# MCU_scm.net
KiCad netlist of a schematic drawn in Altium Designer
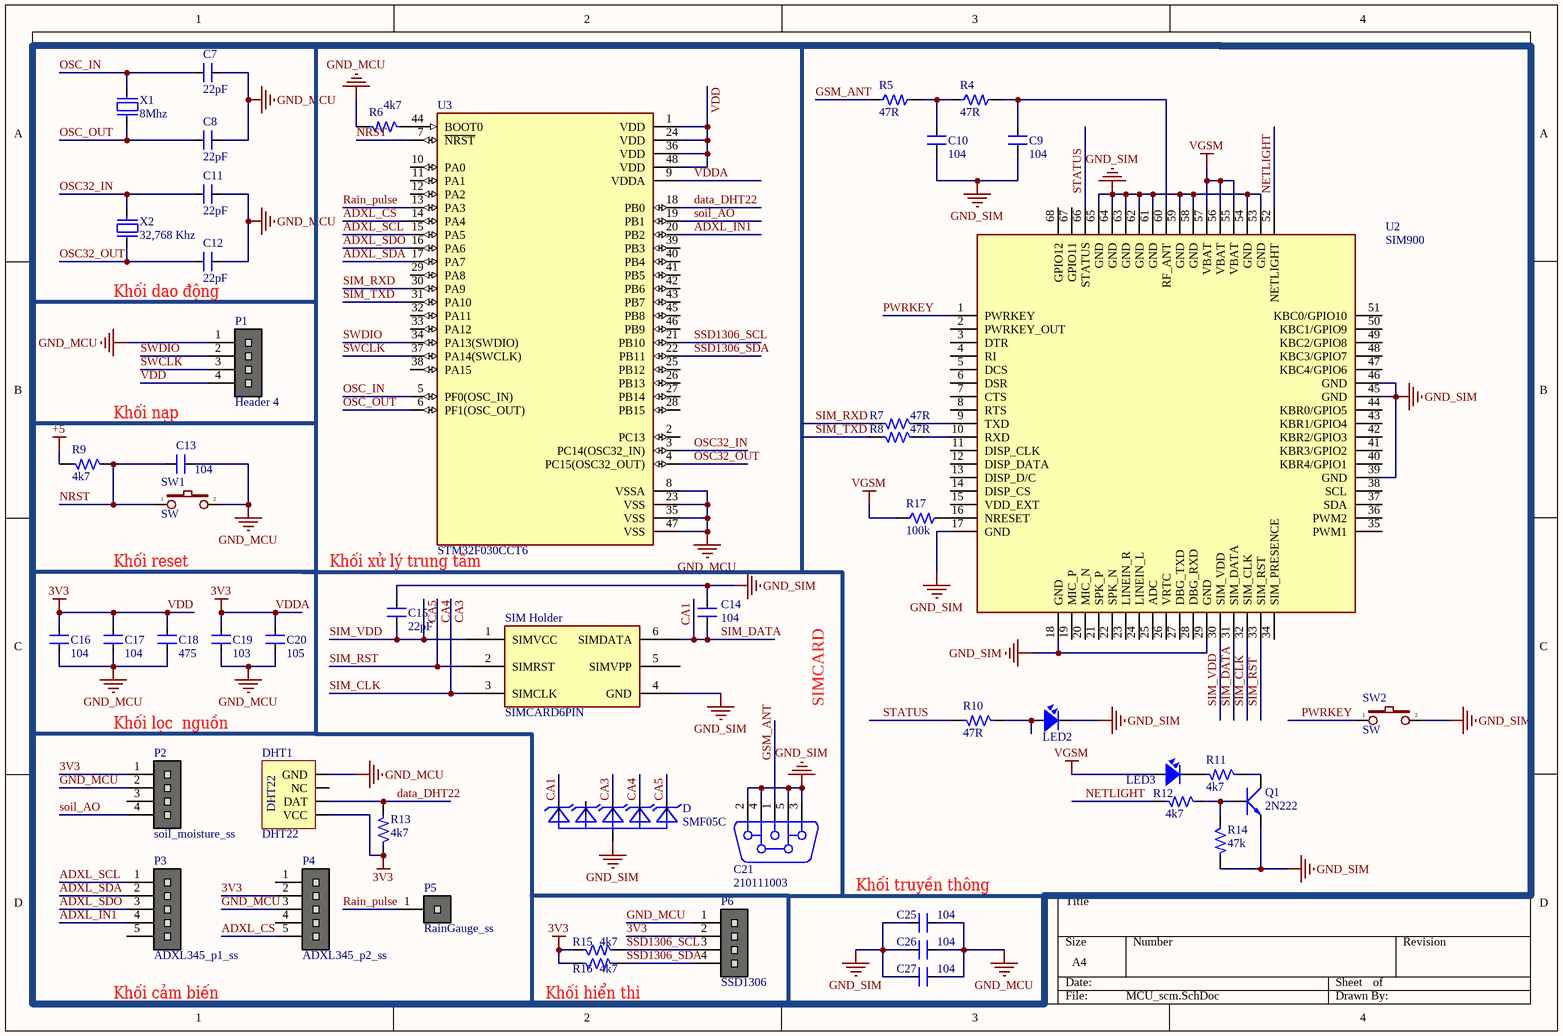
[diagram p0: MCU_scm.SchDoc]

(export (version "E")
  (design (tool "Eeschema 10.0.6"))
  (components
    (comp (ref "C7")
      (value "22pF")
      (footprint "CN1.5")
      (description "Cap np 682pF => 104pF")
      (libsource (lib "syhaunguyen") (part "CN1.5"))
    )
    (comp (ref "C8")
      (value "22pF")
      (footprint "CN1.5")
      (description "Cap np 682pF => 104pF")
      (libsource (lib "syhaunguyen") (part "CN1.5"))
    )
    (comp (ref "C9")
      (value "104")
      (footprint "SM-0805")
      (description "Cap SMD")
      (libsource (lib "syhaunguyen") (part "CM"))
    )
    (comp (ref "C10")
      (value "104")
      (footprint "SM-0805")
      (description "Cap SMD")
      (libsource (lib "syhaunguyen") (part "CM"))
    )
    (comp (ref "C11")
      (value "22pF")
      (footprint "CN1.5")
      (description "Cap np 682pF => 104pF")
      (libsource (lib "syhaunguyen") (part "CN1.5"))
    )
    (comp (ref "C12")
      (value "22pF")
      (footprint "CN1.5")
      (description "Cap np 682pF => 104pF")
      (libsource (lib "syhaunguyen") (part "CN1.5"))
    )
    (comp (ref "C13")
      (value "104")
      (footprint "SM-0805")
      (description "Cap SMD")
      (libsource (lib "syhaunguyen") (part "CM"))
    )
    (comp (ref "C14")
      (value "104")
      (footprint "SM-0805")
      (description "Cap SMD")
      (libsource (lib "syhaunguyen") (part "CM"))
    )
    (comp (ref "C15")
      (value "22pF")
      (footprint "SM-0805")
      (description "Cap SMD")
      (libsource (lib "syhaunguyen") (part "CM"))
    )
    (comp (ref "C16")
      (value "104")
      (footprint "SM-0805")
      (description "Cap SMD")
      (libsource (lib "syhaunguyen") (part "CM"))
    )
    (comp (ref "C17")
      (value "104")
      (footprint "SM-0805")
      (description "Cap SMD")
      (libsource (lib "syhaunguyen") (part "CM"))
    )
    (comp (ref "C18")
      (value "475")
      (footprint "SM-0805")
      (description "Cap SMD")
      (libsource (lib "syhaunguyen") (part "CM"))
    )
    (comp (ref "C19")
      (value "103")
      (footprint "SM-0805")
      (description "Cap SMD")
      (libsource (lib "syhaunguyen") (part "CM"))
    )
    (comp (ref "C20")
      (value "105")
      (footprint "SM-0805")
      (description "Cap SMD")
      (libsource (lib "syhaunguyen") (part "CM"))
    )
    (comp (ref "C21")
      (value "210111003")
      (footprint "SMA-RA")
      (description "CONNECTOR ANTEN")
      (fields
        (field (name "MANUFACTURER") "Würth Elektronik eiSos GmbH")
        (field (name "CREATED BY") "Christin Zierenner")
      )
      (libsource (lib "TechMT.VN_Lib_Project v2") (part "CON Ant"))
    )
    (comp (ref "C25")
      (value "104")
      (footprint "SM-0805")
      (description "Cap SMD")
      (libsource (lib "syhaunguyen") (part "CM"))
    )
    (comp (ref "C26")
      (value "104")
      (footprint "SM-0805")
      (description "Cap SMD")
      (libsource (lib "syhaunguyen") (part "CM"))
    )
    (comp (ref "C27")
      (value "104")
      (footprint "SM-0805")
      (description "Cap SMD")
      (libsource (lib "syhaunguyen") (part "CM"))
    )
    (comp (ref "D")
      (value "SMF05C")
      (footprint "SC70-6")
      (description "12.5V Clamp 8A _8/20Âµs_ Ipp Tvs Diode Surface Mount SC-88/SC70-6/SOT-363")
      (fields (field (name "MF") "ON Semiconductor"))
      (libsource (lib "SMF05C") (part "SMF05C"))
    )
    (comp (ref "DHT1")
      (value "DHT22")
      (footprint "DHT22")
      (fields
        (field (name "MANUFACTURER") "Würth Elektronik eiSos GmbH")
        (field (name "PARTNO") "613004143121")
        (field (name "CREATED BY") "Karrer Zheng")
      )
      (libsource (lib "TechMT.VN_Lib_Project v2") (part "DHT22"))
    )
    (comp (ref "LED2")
      (value "LED")
      (footprint "LED-0805-Green")
      (libsource (lib "TechMT.VN_Lib_Project v2") (part "LED SMD"))
    )
    (comp (ref "LED3")
      (value "LED")
      (footprint "LED-0805-Green")
      (libsource (lib "TechMT.VN_Lib_Project v2") (part "LED SMD"))
    )
    (comp (ref "P1")
      (value "Header 4")
      (footprint "HDR 1X4")
      (description "Header, 4-Pin")
      (libsource (lib "Ayric connectors") (part "Header 4"))
    )
    (comp (ref "P2")
      (value "soil_moisture_ss")
      (footprint "HDR 1X4")
      (description "Header, 4-Pin")
      (libsource (lib "Ayric connectors") (part "Header 4"))
    )
    (comp (ref "P3")
      (value "ADXL345_p1_ss")
      (footprint "HDR 1X5")
      (description "Header, 5-Pin")
      (libsource (lib "Ayric connectors") (part "Header 5"))
    )
    (comp (ref "P4")
      (value "ADXL345_p2_ss")
      (footprint "HDR 1X5")
      (description "Header, 5-Pin")
      (libsource (lib "Ayric connectors") (part "Header 5"))
    )
    (comp (ref "P5")
      (value "RainGauge_ss")
      (footprint "HDR 1X1")
      (description "Header, 1-Pin")
      (libsource (lib "Ayric connectors") (part "Header 1"))
    )
    (comp (ref "P6")
      (value "SSD1306")
      (footprint "HDR 1X4")
      (description "Header, 4-Pin")
      (libsource (lib "Ayric connectors") (part "Header 4"))
    )
    (comp (ref "Q1")
      (value "2N222")
      (footprint "TO92-123")
      (description "NPN 600mW, ECB")
      (fields (field (name "CREAT BY") "MT-TECH.VN"))
      (libsource (lib "TechMT.VN_Lib_Project v2") (part "2N222"))
    )
    (comp (ref "R4")
      (value "47R")
      (footprint "R-0805")
      (description "dien tro")
      (libsource (lib "oggy") (part "resistor"))
    )
    (comp (ref "R5")
      (value "47R")
      (footprint "R-0805")
      (description "dien tro")
      (libsource (lib "oggy") (part "resistor"))
    )
    (comp (ref "R6")
      (value "4k7")
      (footprint "R-0805")
      (description "dien tro")
      (libsource (lib "oggy") (part "resistor"))
    )
    (comp (ref "R7")
      (value "47R")
      (footprint "R-0805")
      (description "dien tro")
      (libsource (lib "oggy") (part "resistor"))
    )
    (comp (ref "R8")
      (value "47R")
      (footprint "R-0805")
      (description "dien tro")
      (libsource (lib "oggy") (part "resistor"))
    )
    (comp (ref "R9")
      (value "4k7")
      (footprint "R-0805")
      (description "dien tro")
      (libsource (lib "oggy") (part "resistor"))
    )
    (comp (ref "R10")
      (value "47R")
      (footprint "R-0805")
      (description "dien tro")
      (libsource (lib "oggy") (part "resistor"))
    )
    (comp (ref "R11")
      (value "4k7")
      (footprint "R-0805")
      (description "dien tro")
      (libsource (lib "oggy") (part "resistor"))
    )
    (comp (ref "R12")
      (value "4k7")
      (footprint "R-0805")
      (description "dien tro")
      (libsource (lib "oggy") (part "resistor"))
    )
    (comp (ref "R13")
      (value "4k7")
      (footprint "R-0805")
      (description "dien tro")
      (libsource (lib "oggy") (part "resistor"))
    )
    (comp (ref "R14")
      (value "47k")
      (footprint "R-0805")
      (description "dien tro")
      (libsource (lib "oggy") (part "resistor"))
    )
    (comp (ref "R15")
      (value "4k7")
      (footprint "R-0805")
      (description "dien tro")
      (libsource (lib "oggy") (part "resistor"))
    )
    (comp (ref "R16")
      (value "4k7")
      (footprint "R-0805")
      (description "dien tro")
      (libsource (lib "oggy") (part "resistor"))
    )
    (comp (ref "R17")
      (value "100k")
      (footprint "R-0805")
      (description "dien tro")
      (libsource (lib "oggy") (part "resistor"))
    )
    (comp (ref "SIM Holder")
      (value "SIMCARD6PIN")
      (footprint "SIMCARD6pin")
      (libsource (lib "AYRIC Library") (part "SIMCARD6PIN"))
    )
    (comp (ref "SW1")
      (value "SW")
      (footprint "SW1-SMD")
      (description "Switch button 2 pin")
      (libsource (lib "TechMT.VN_Lib_Project v2") (part "SW2"))
    )
    (comp (ref "SW2")
      (value "SW")
      (footprint "SW1-SMD")
      (description "Switch button 2 pin")
      (libsource (lib "TechMT.VN_Lib_Project v2") (part "SW2"))
    )
    (comp (ref "U2") (value "SIM900") (footprint "SIM900") (libsource (lib "AYRIC Library") (part "SIM900")))
    (comp (ref "U3")
      (value "STM32F030CCT6")
      (footprint "QFP50P900X900X160-48N")
      (description "ARMÂ® CortexÂ®-M0 STM32F0 Microcontroller IC 32-Bit 48MHz 256KB _256K x 8_ FLASH 48-LQFP _7x7_")
      (fields (field (name "MF") "STMicroelectronics") (field (name "DIGI-KEY_PART_NUMBER") "497-17332-2-ND"))
      (libsource (lib "STM32F030CCT6") (part "STM32F030CCT6"))
    )
    (comp (ref "X1")
      (value "8Mhz")
      (footprint "XT2")
      (description "Crystal For all Crystal 2pin.")
      (libsource (lib "syhaunguyen") (part "XT2"))
    )
    (comp (ref "X2")
      (value "32,768 Khz")
      (footprint "XT32k")
      (description "Crystal 32,768kHz for timer real")
      (libsource (lib "syhaunguyen") (part "XT32k"))
    )
  )
  (nets
    (net (code "1") (name "+5") (class "Default")
      (node (ref "R9") (pin "2") (pinfunction "2_2") (pintype "passive"))
    )
    (net (code "2") (name "/ADXL_CS") (class "Default")
      (node (ref "P4") (pin "5") (pinfunction "5_5") (pintype "passive"))
      (node (ref "U3") (pin "14") (pinfunction "PA4_14") (pintype "bidirectional"))
    )
    (net (code "3") (name "/ADXL_IN1") (class "Default")
      (node (ref "P3") (pin "4") (pinfunction "4_4") (pintype "passive"))
      (node (ref "U3") (pin "20") (pinfunction "PB2_20") (pintype "bidirectional"))
    )
    (net (code "4") (name "/ADXL_SCL") (class "Default")
      (node (ref "P3") (pin "1") (pinfunction "1_1") (pintype "passive"))
      (node (ref "U3") (pin "15") (pinfunction "PA5_15") (pintype "bidirectional"))
    )
    (net (code "5") (name "/ADXL_SDA") (class "Default")
      (node (ref "P3") (pin "2") (pinfunction "2_2") (pintype "passive"))
      (node (ref "U3") (pin "17") (pinfunction "PA7_17") (pintype "bidirectional"))
    )
    (net (code "6") (name "/ADXL_SDO") (class "Default")
      (node (ref "P3") (pin "3") (pinfunction "3_3") (pintype "passive"))
      (node (ref "U3") (pin "16") (pinfunction "PA6_16") (pintype "bidirectional"))
    )
    (net (code "7") (name "/CA1") (class "Default")
      (node (ref "C14") (pin "1") (pinfunction "1_1") (pintype "passive"))
      (node (ref "D") (pin "1") (pinfunction "C1_1") (pintype "passive"))
      (node (ref "SIM Holder") (pin "6") (pinfunction "SIMDATA_6") (pintype "passive"))
      (node (ref "U2") (pin "31") (pinfunction "SIM_DATA_31") (pintype "passive"))
    )
    (net (code "8") (name "/CA3") (class "Default")
      (node (ref "D") (pin "4") (pinfunction "C3_4") (pintype "passive"))
      (node (ref "SIM Holder") (pin "3") (pinfunction "SIMCLK_3") (pintype "passive"))
      (node (ref "U2") (pin "32") (pinfunction "SIM_CLK_32") (pintype "passive"))
    )
    (net (code "9") (name "/CA4") (class "Default")
      (node (ref "D") (pin "5") (pinfunction "C4_5") (pintype "passive"))
      (node (ref "SIM Holder") (pin "2") (pinfunction "SIMRST_2") (pintype "passive"))
      (node (ref "U2") (pin "33") (pinfunction "SIM_RST_33") (pintype "passive"))
    )
    (net (code "10") (name "/CA5") (class "Default")
      (node (ref "C15") (pin "1") (pinfunction "1_1") (pintype "passive"))
      (node (ref "D") (pin "6") (pinfunction "C5_6") (pintype "passive"))
      (node (ref "SIM Holder") (pin "1") (pinfunction "SIMVCC_1") (pintype "passive"))
      (node (ref "U2") (pin "30") (pinfunction "SIM_VDD_30") (pintype "passive"))
    )
    (net (code "11") (name "/GSM_ANT") (class "Default")
      (node (ref "C21") (pin "1") (pinfunction "1_1") (pintype "passive"))
      (node (ref "R5") (pin "1") (pinfunction "1_1") (pintype "passive"))
    )
    (net (code "12") (name "/NETLIGHT") (class "Default")
      (node (ref "R12") (pin "2") (pinfunction "2_2") (pintype "passive"))
      (node (ref "U2") (pin "52") (pinfunction "NETLIGHT_52") (pintype "passive"))
    )
    (net (code "13") (name "/NRST") (class "Default")
      (node (ref "C13") (pin "1") (pinfunction "1_1") (pintype "passive"))
      (node (ref "R9") (pin "1") (pinfunction "1_1") (pintype "passive"))
      (node (ref "SW1") (pin "1") (pinfunction "1_1") (pintype "passive"))
      (node (ref "U3") (pin "7") (pinfunction "~{NRST}_7") (pintype "bidirectional"))
    )
    (net (code "14") (name "/OSC32_IN") (class "Default")
      (node (ref "C11") (pin "2") (pinfunction "2_2") (pintype "passive"))
      (node (ref "U3") (pin "3") (pinfunction "PC14(OSC32_IN)_3") (pintype "bidirectional"))
      (node (ref "X2") (pin "2") (pinfunction "2_2") (pintype "passive"))
    )
    (net (code "15") (name "/OSC32_OUT") (class "Default")
      (node (ref "C12") (pin "2") (pinfunction "2_2") (pintype "passive"))
      (node (ref "U3") (pin "4") (pinfunction "PC15(OSC32_OUT)_4") (pintype "bidirectional"))
      (node (ref "X2") (pin "1") (pinfunction "1_1") (pintype "passive"))
    )
    (net (code "16") (name "/OSC_IN") (class "Default")
      (node (ref "C7") (pin "2") (pinfunction "2_2") (pintype "passive"))
      (node (ref "U3") (pin "5") (pinfunction "PF0(OSC_IN)_5") (pintype "bidirectional"))
      (node (ref "X1") (pin "2") (pinfunction "2_2") (pintype "passive"))
    )
    (net (code "17") (name "/OSC_OUT") (class "Default")
      (node (ref "C8") (pin "2") (pinfunction "2_2") (pintype "passive"))
      (node (ref "U3") (pin "6") (pinfunction "PF1(OSC_OUT)_6") (pintype "bidirectional"))
      (node (ref "X1") (pin "1") (pinfunction "1_1") (pintype "passive"))
    )
    (net (code "18") (name "/PWRKEY") (class "Default")
      (node (ref "SW2") (pin "1") (pinfunction "1_1") (pintype "passive"))
      (node (ref "U2") (pin "1") (pinfunction "PWRKEY_1") (pintype "passive"))
    )
    (net (code "19") (name "/Rain_pulse") (class "Default")
      (node (ref "P5") (pin "1") (pinfunction "1_1") (pintype "passive"))
      (node (ref "U3") (pin "13") (pinfunction "PA3_13") (pintype "bidirectional"))
    )
    (net (code "20") (name "/SIM_RXD") (class "Default")
      (node (ref "R7") (pin "2") (pinfunction "2_2") (pintype "passive"))
      (node (ref "U3") (pin "30") (pinfunction "PA9_30") (pintype "bidirectional"))
    )
    (net (code "21") (name "/SIM_TXD") (class "Default")
      (node (ref "R8") (pin "2") (pinfunction "2_2") (pintype "passive"))
      (node (ref "U3") (pin "31") (pinfunction "PA10_31") (pintype "bidirectional"))
    )
    (net (code "22") (name "/SSD1306_SCL") (class "Default")
      (node (ref "P6") (pin "3") (pinfunction "3_3") (pintype "passive"))
      (node (ref "R15") (pin "2") (pinfunction "2_2") (pintype "passive"))
      (node (ref "U3") (pin "21") (pinfunction "PB10_21") (pintype "bidirectional"))
    )
    (net (code "23") (name "/SSD1306_SDA") (class "Default")
      (node (ref "P6") (pin "4") (pinfunction "4_4") (pintype "passive"))
      (node (ref "R16") (pin "2") (pinfunction "2_2") (pintype "passive"))
      (node (ref "U3") (pin "22") (pinfunction "PB11_22") (pintype "bidirectional"))
    )
    (net (code "24") (name "/STATUS") (class "Default")
      (node (ref "R10") (pin "2") (pinfunction "2_2") (pintype "passive"))
      (node (ref "U2") (pin "66") (pinfunction "STATUS_66") (pintype "passive"))
    )
    (net (code "25") (name "/SWCLK") (class "Default")
      (node (ref "P1") (pin "3") (pinfunction "3_3") (pintype "passive"))
      (node (ref "U3") (pin "37") (pinfunction "PA14(SWCLK)_37") (pintype "bidirectional"))
    )
    (net (code "26") (name "/SWDIO") (class "Default")
      (node (ref "P1") (pin "2") (pinfunction "2_2") (pintype "passive"))
      (node (ref "U3") (pin "34") (pinfunction "PA13(SWDIO)_34") (pintype "bidirectional"))
    )
    (net (code "27") (name "/data_DHT22") (class "Default")
      (node (ref "DHT1") (pin "2") (pinfunction "DAT_2") (pintype "passive"))
      (node (ref "R13") (pin "2") (pinfunction "2_2") (pintype "passive"))
      (node (ref "U3") (pin "18") (pinfunction "PB0_18") (pintype "bidirectional"))
    )
    (net (code "28") (name "/soil_AO") (class "Default")
      (node (ref "P2") (pin "4") (pinfunction "4_4") (pintype "passive"))
      (node (ref "U3") (pin "19") (pinfunction "PB1_19") (pintype "bidirectional"))
    )
    (net (code "29") (name "3V3") (class "Default")
      (node (ref "C16") (pin "2") (pinfunction "2_2") (pintype "passive"))
      (node (ref "C17") (pin "2") (pinfunction "2_2") (pintype "passive"))
      (node (ref "C18") (pin "2") (pinfunction "2_2") (pintype "passive"))
      (node (ref "C19") (pin "2") (pinfunction "2_2") (pintype "passive"))
      (node (ref "C20") (pin "2") (pinfunction "2_2") (pintype "passive"))
      (node (ref "DHT1") (pin "1") (pinfunction "VCC_1") (pintype "passive"))
      (node (ref "P1") (pin "4") (pinfunction "4_4") (pintype "passive"))
      (node (ref "P2") (pin "1") (pinfunction "1_1") (pintype "passive"))
      (node (ref "P4") (pin "2") (pinfunction "2_2") (pintype "passive"))
      (node (ref "P6") (pin "2") (pinfunction "2_2") (pintype "passive"))
      (node (ref "R13") (pin "1") (pinfunction "1_1") (pintype "passive"))
      (node (ref "R15") (pin "1") (pinfunction "1_1") (pintype "passive"))
      (node (ref "R16") (pin "1") (pinfunction "1_1") (pintype "passive"))
      (node (ref "U3") (pin "1") (pinfunction "VDD_1") (pintype "power_in"))
      (node (ref "U3") (pin "24") (pinfunction "VDD_24") (pintype "power_in"))
      (node (ref "U3") (pin "36") (pinfunction "VDD_36") (pintype "power_in"))
      (node (ref "U3") (pin "48") (pinfunction "VDD_48") (pintype "power_in"))
      (node (ref "U3") (pin "9") (pinfunction "VDDA_9") (pintype "power_in"))
    )
    (net (code "30") (name "GND_MCU") (class "Default")
      (node (ref "C11") (pin "1") (pinfunction "1_1") (pintype "passive"))
      (node (ref "C12") (pin "1") (pinfunction "1_1") (pintype "passive"))
      (node (ref "C13") (pin "2") (pinfunction "2_2") (pintype "passive"))
      (node (ref "C16") (pin "1") (pinfunction "1_1") (pintype "passive"))
      (node (ref "C17") (pin "1") (pinfunction "1_1") (pintype "passive"))
      (node (ref "C18") (pin "1") (pinfunction "1_1") (pintype "passive"))
      (node (ref "C19") (pin "1") (pinfunction "1_1") (pintype "passive"))
      (node (ref "C20") (pin "1") (pinfunction "1_1") (pintype "passive"))
      (node (ref "C25") (pin "2") (pinfunction "2_2") (pintype "passive"))
      (node (ref "C26") (pin "2") (pinfunction "2_2") (pintype "passive"))
      (node (ref "C27") (pin "2") (pinfunction "2_2") (pintype "passive"))
      (node (ref "C7") (pin "1") (pinfunction "1_1") (pintype "passive"))
      (node (ref "C8") (pin "1") (pinfunction "1_1") (pintype "passive"))
      (node (ref "DHT1") (pin "4") (pinfunction "GND_4") (pintype "passive"))
      (node (ref "P1") (pin "1") (pinfunction "1_1") (pintype "passive"))
      (node (ref "P2") (pin "2") (pinfunction "2_2") (pintype "passive"))
      (node (ref "P4") (pin "3") (pinfunction "3_3") (pintype "passive"))
      (node (ref "P6") (pin "1") (pinfunction "1_1") (pintype "passive"))
      (node (ref "R6") (pin "2") (pinfunction "2_2") (pintype "passive"))
      (node (ref "SW1") (pin "2") (pinfunction "2_2") (pintype "passive"))
      (node (ref "U3") (pin "23") (pinfunction "VSS_23") (pintype "power_in"))
      (node (ref "U3") (pin "35") (pinfunction "VSS_35") (pintype "power_in"))
      (node (ref "U3") (pin "47") (pinfunction "VSS_47") (pintype "power_in"))
      (node (ref "U3") (pin "8") (pinfunction "VSSA_8") (pintype "power_in"))
    )
    (net (code "31") (name "GND_SIM") (class "Default")
      (node (ref "C10") (pin "1") (pinfunction "1_1") (pintype "passive"))
      (node (ref "C14") (pin "2") (pinfunction "2_2") (pintype "passive"))
      (node (ref "C15") (pin "2") (pinfunction "2_2") (pintype "passive"))
      (node (ref "C21") (pin "2") (pinfunction "2_2") (pintype "passive"))
      (node (ref "C21") (pin "3") (pinfunction "3_3") (pintype "passive"))
      (node (ref "C21") (pin "4") (pinfunction "4_4") (pintype "passive"))
      (node (ref "C21") (pin "5") (pinfunction "5_5") (pintype "passive"))
      (node (ref "C25") (pin "1") (pinfunction "1_1") (pintype "passive"))
      (node (ref "C26") (pin "1") (pinfunction "1_1") (pintype "passive"))
      (node (ref "C27") (pin "1") (pinfunction "1_1") (pintype "passive"))
      (node (ref "C9") (pin "1") (pinfunction "1_1") (pintype "passive"))
      (node (ref "D") (pin "2") (pinfunction "A_2") (pintype "passive"))
      (node (ref "LED2") (pin "2") (pinfunction "2_2") (pintype "passive"))
      (node (ref "Q1") (pin "1") (pinfunction "E_1") (pintype "passive"))
      (node (ref "R14") (pin "2") (pinfunction "2_2") (pintype "passive"))
      (node (ref "SIM Holder") (pin "4") (pinfunction "GND_4") (pintype "passive"))
      (node (ref "SW2") (pin "2") (pinfunction "2_2") (pintype "passive"))
      (node (ref "U2") (pin "17") (pinfunction "GND_17") (pintype "passive"))
      (node (ref "U2") (pin "18") (pinfunction "GND_18") (pintype "passive"))
      (node (ref "U2") (pin "29") (pinfunction "GND_29") (pintype "passive"))
      (node (ref "U2") (pin "39") (pinfunction "GND_39") (pintype "passive"))
      (node (ref "U2") (pin "45") (pinfunction "GND_45") (pintype "passive"))
      (node (ref "U2") (pin "46") (pinfunction "GND_46") (pintype "passive"))
      (node (ref "U2") (pin "53") (pinfunction "GND_53") (pintype "passive"))
      (node (ref "U2") (pin "54") (pinfunction "GND_54") (pintype "passive"))
      (node (ref "U2") (pin "58") (pinfunction "GND_58") (pintype "passive"))
      (node (ref "U2") (pin "59") (pinfunction "GND_59") (pintype "passive"))
      (node (ref "U2") (pin "61") (pinfunction "GND_61") (pintype "passive"))
      (node (ref "U2") (pin "62") (pinfunction "GND_62") (pintype "passive"))
      (node (ref "U2") (pin "63") (pinfunction "GND_63") (pintype "passive"))
      (node (ref "U2") (pin "64") (pinfunction "GND_64") (pintype "passive"))
      (node (ref "U2") (pin "65") (pinfunction "GND_65") (pintype "passive"))
    )
    (net (code "32") (name "Net-(C10-Pad2)") (class "Default")
      (node (ref "C10") (pin "2") (pinfunction "2_2") (pintype "passive"))
      (node (ref "R4") (pin "1") (pinfunction "1_1") (pintype "passive"))
      (node (ref "R5") (pin "2") (pinfunction "2_2") (pintype "passive"))
    )
    (net (code "33") (name "Net-(LED2-Pad1)") (class "Default")
      (node (ref "LED2") (pin "1") (pinfunction "1_1") (pintype "passive"))
      (node (ref "R10") (pin "1") (pinfunction "1_1") (pintype "passive"))
    )
    (net (code "34") (name "Net-(LED3-Pad2)") (class "Default")
      (node (ref "LED3") (pin "2") (pinfunction "2_2") (pintype "passive"))
      (node (ref "R11") (pin "2") (pinfunction "2_2") (pintype "passive"))
    )
    (net (code "35") (name "Net-(Q1-B)") (class "Default")
      (node (ref "Q1") (pin "2") (pinfunction "B_2") (pintype "passive"))
      (node (ref "R12") (pin "1") (pinfunction "1_1") (pintype "passive"))
      (node (ref "R14") (pin "1") (pinfunction "1_1") (pintype "passive"))
    )
    (net (code "36") (name "Net-(Q1-C)") (class "Default")
      (node (ref "Q1") (pin "3") (pinfunction "C_3") (pintype "passive"))
      (node (ref "R11") (pin "1") (pinfunction "1_1") (pintype "passive"))
    )
    (net (code "37") (name "Net-(U2-NRESET)") (class "Default")
      (node (ref "R17") (pin "2") (pinfunction "2_2") (pintype "passive"))
      (node (ref "U2") (pin "16") (pinfunction "NRESET_16") (pintype "passive"))
    )
    (net (code "38") (name "Net-(U2-RF_ANT)") (class "Default")
      (node (ref "C9") (pin "2") (pinfunction "2_2") (pintype "passive"))
      (node (ref "R4") (pin "2") (pinfunction "2_2") (pintype "passive"))
      (node (ref "U2") (pin "60") (pinfunction "RF_ANT_60") (pintype "passive"))
    )
    (net (code "39") (name "Net-(U2-RXD)") (class "Default")
      (node (ref "R8") (pin "1") (pinfunction "1_1") (pintype "passive"))
      (node (ref "U2") (pin "10") (pinfunction "RXD_10") (pintype "passive"))
    )
    (net (code "40") (name "Net-(U2-TXD)") (class "Default")
      (node (ref "R7") (pin "1") (pinfunction "1_1") (pintype "passive"))
      (node (ref "U2") (pin "9") (pinfunction "TXD_9") (pintype "passive"))
    )
    (net (code "41") (name "Net-(U3-BOOT0)") (class "Default")
      (node (ref "R6") (pin "1") (pinfunction "1_1") (pintype "passive"))
      (node (ref "U3") (pin "44") (pinfunction "BOOT0_44") (pintype "input"))
    )
    (net (code "42") (name "VGSM") (class "Default")
      (node (ref "LED3") (pin "1") (pinfunction "1_1") (pintype "passive"))
      (node (ref "R17") (pin "1") (pinfunction "1_1") (pintype "passive"))
      (node (ref "U2") (pin "55") (pinfunction "VBAT_55") (pintype "passive"))
      (node (ref "U2") (pin "56") (pinfunction "VBAT_56") (pintype "passive"))
      (node (ref "U2") (pin "57") (pinfunction "VBAT_57") (pintype "passive"))
    )
    (net (code "43") (name "unconnected-(D-C2-Pad3)") (class "Default")
      (node (ref "D") (pin "3") (pinfunction "C2_3") (pintype "passive"))
    )
    (net (code "44") (name "unconnected-(DHT1-NC-Pad3)") (class "Default")
      (node (ref "DHT1") (pin "3") (pinfunction "NC_3") (pintype "passive"))
    )
    (net (code "45") (name "unconnected-(P2-Pad3)") (class "Default")
      (node (ref "P2") (pin "3") (pinfunction "3_3") (pintype "passive"))
    )
    (net (code "46") (name "unconnected-(P3-Pad5)") (class "Default")
      (node (ref "P3") (pin "5") (pinfunction "5_5") (pintype "passive"))
    )
    (net (code "47") (name "unconnected-(P4-Pad1)") (class "Default")
      (node (ref "P4") (pin "1") (pinfunction "1_1") (pintype "passive"))
    )
    (net (code "48") (name "unconnected-(P4-Pad4)") (class "Default")
      (node (ref "P4") (pin "4") (pinfunction "4_4") (pintype "passive"))
    )
    (net (code "49") (name "unconnected-(SIM Holder-SIMVPP-Pad5)") (class "Default")
      (node (ref "SIM Holder") (pin "5") (pinfunction "SIMVPP_5") (pintype "passive"))
    )
    (net (code "50") (name "unconnected-(U2-ADC-Pad25)") (class "Default")
      (node (ref "U2") (pin "25") (pinfunction "ADC_25") (pintype "passive"))
    )
    (net (code "51") (name "unconnected-(U2-CTS-Pad7)") (class "Default")
      (node (ref "U2") (pin "7") (pinfunction "CTS_7") (pintype "passive"))
    )
    (net (code "52") (name "unconnected-(U2-DBG_RXD-Pad28)") (class "Default")
      (node (ref "U2") (pin "28") (pinfunction "DBG_RXD_28") (pintype "passive"))
    )
    (net (code "53") (name "unconnected-(U2-DBG_TXD-Pad27)") (class "Default")
      (node (ref "U2") (pin "27") (pinfunction "DBG_TXD_27") (pintype "passive"))
    )
    (net (code "54") (name "unconnected-(U2-DCS-Pad5)") (class "Default")
      (node (ref "U2") (pin "5") (pinfunction "DCS_5") (pintype "passive"))
    )
    (net (code "55") (name "unconnected-(U2-DISP_CLK-Pad11)") (class "Default")
      (node (ref "U2") (pin "11") (pinfunction "DISP_CLK_11") (pintype "passive"))
    )
    (net (code "56") (name "unconnected-(U2-DISP_CS-Pad14)") (class "Default")
      (node (ref "U2") (pin "14") (pinfunction "DISP_CS_14") (pintype "passive"))
    )
    (net (code "57") (name "unconnected-(U2-DISP_DATA-Pad12)") (class "Default")
      (node (ref "U2") (pin "12") (pinfunction "DISP_DATA_12") (pintype "passive"))
    )
    (net (code "58") (name "unconnected-(U2-DISP_D{slash}C-Pad13)") (class "Default")
      (node (ref "U2") (pin "13") (pinfunction "DISP_D/C_13") (pintype "passive"))
    )
    (net (code "59") (name "unconnected-(U2-DSR-Pad6)") (class "Default")
      (node (ref "U2") (pin "6") (pinfunction "DSR_6") (pintype "passive"))
    )
    (net (code "60") (name "unconnected-(U2-DTR-Pad3)") (class "Default")
      (node (ref "U2") (pin "3") (pinfunction "DTR_3") (pintype "passive"))
    )
    (net (code "61") (name "unconnected-(U2-GPIO11-Pad67)") (class "Default")
      (node (ref "U2") (pin "67") (pinfunction "GPIO11_67") (pintype "passive"))
    )
    (net (code "62") (name "unconnected-(U2-GPIO12-Pad68)") (class "Default")
      (node (ref "U2") (pin "68") (pinfunction "GPIO12_68") (pintype "passive"))
    )
    (net (code "63") (name "unconnected-(U2-KBC0{slash}GPIO10-Pad51)") (class "Default")
      (node (ref "U2") (pin "51") (pinfunction "KBC0/GPIO10_51") (pintype "passive"))
    )
    (net (code "64") (name "unconnected-(U2-KBC1{slash}GPIO9-Pad50)") (class "Default")
      (node (ref "U2") (pin "50") (pinfunction "KBC1/GPIO9_50") (pintype "passive"))
    )
    (net (code "65") (name "unconnected-(U2-KBC2{slash}GPIO8-Pad49)") (class "Default")
      (node (ref "U2") (pin "49") (pinfunction "KBC2/GPIO8_49") (pintype "passive"))
    )
    (net (code "66") (name "unconnected-(U2-KBC3{slash}GPIO7-Pad48)") (class "Default")
      (node (ref "U2") (pin "48") (pinfunction "KBC3/GPIO7_48") (pintype "passive"))
    )
    (net (code "67") (name "unconnected-(U2-KBC4{slash}GPIO6-Pad47)") (class "Default")
      (node (ref "U2") (pin "47") (pinfunction "KBC4/GPIO6_47") (pintype "passive"))
    )
    (net (code "68") (name "unconnected-(U2-KBR0{slash}GPIO5-Pad44)") (class "Default")
      (node (ref "U2") (pin "44") (pinfunction "KBR0/GPIO5_44") (pintype "passive"))
    )
    (net (code "69") (name "unconnected-(U2-KBR1{slash}GPIO4-Pad43)") (class "Default")
      (node (ref "U2") (pin "43") (pinfunction "KBR1/GPIO4_43") (pintype "passive"))
    )
    (net (code "70") (name "unconnected-(U2-KBR2{slash}GPIO3-Pad42)") (class "Default")
      (node (ref "U2") (pin "42") (pinfunction "KBR2/GPIO3_42") (pintype "passive"))
    )
    (net (code "71") (name "unconnected-(U2-KBR3{slash}GPIO2-Pad41)") (class "Default")
      (node (ref "U2") (pin "41") (pinfunction "KBR3/GPIO2_41") (pintype "passive"))
    )
    (net (code "72") (name "unconnected-(U2-KBR4{slash}GPIO1-Pad40)") (class "Default")
      (node (ref "U2") (pin "40") (pinfunction "KBR4/GPIO1_40") (pintype "passive"))
    )
    (net (code "73") (name "unconnected-(U2-LINEIN_L-Pad24)") (class "Default")
      (node (ref "U2") (pin "24") (pinfunction "LINEIN_L_24") (pintype "passive"))
    )
    (net (code "74") (name "unconnected-(U2-LINEIN_R-Pad23)") (class "Default")
      (node (ref "U2") (pin "23") (pinfunction "LINEIN_R_23") (pintype "passive"))
    )
    (net (code "75") (name "unconnected-(U2-MIC_N-Pad20)") (class "Default")
      (node (ref "U2") (pin "20") (pinfunction "MIC_N_20") (pintype "passive"))
    )
    (net (code "76") (name "unconnected-(U2-MIC_P-Pad19)") (class "Default")
      (node (ref "U2") (pin "19") (pinfunction "MIC_P_19") (pintype "passive"))
    )
    (net (code "77") (name "unconnected-(U2-PWM1-Pad35)") (class "Default")
      (node (ref "U2") (pin "35") (pinfunction "PWM1_35") (pintype "passive"))
    )
    (net (code "78") (name "unconnected-(U2-PWM2-Pad36)") (class "Default")
      (node (ref "U2") (pin "36") (pinfunction "PWM2_36") (pintype "passive"))
    )
    (net (code "79") (name "unconnected-(U2-PWRKEY_OUT-Pad2)") (class "Default")
      (node (ref "U2") (pin "2") (pinfunction "PWRKEY_OUT_2") (pintype "passive"))
    )
    (net (code "80") (name "unconnected-(U2-RI-Pad4)") (class "Default")
      (node (ref "U2") (pin "4") (pinfunction "RI_4") (pintype "passive"))
    )
    (net (code "81") (name "unconnected-(U2-RTS-Pad8)") (class "Default")
      (node (ref "U2") (pin "8") (pinfunction "RTS_8") (pintype "passive"))
    )
    (net (code "82") (name "unconnected-(U2-SCL-Pad38)") (class "Default")
      (node (ref "U2") (pin "38") (pinfunction "SCL_38") (pintype "passive"))
    )
    (net (code "83") (name "unconnected-(U2-SDA-Pad37)") (class "Default")
      (node (ref "U2") (pin "37") (pinfunction "SDA_37") (pintype "passive"))
    )
    (net (code "84") (name "unconnected-(U2-SIM_PRESENCE-Pad34)") (class "Default")
      (node (ref "U2") (pin "34") (pinfunction "SIM_PRESENCE_34") (pintype "passive"))
    )
    (net (code "85") (name "unconnected-(U2-SPK_N-Pad22)") (class "Default")
      (node (ref "U2") (pin "22") (pinfunction "SPK_N_22") (pintype "passive"))
    )
    (net (code "86") (name "unconnected-(U2-SPK_P-Pad21)") (class "Default")
      (node (ref "U2") (pin "21") (pinfunction "SPK_P_21") (pintype "passive"))
    )
    (net (code "87") (name "unconnected-(U2-VDD_EXT-Pad15)") (class "Default")
      (node (ref "U2") (pin "15") (pinfunction "VDD_EXT_15") (pintype "passive"))
    )
    (net (code "88") (name "unconnected-(U2-VRTC-Pad26)") (class "Default")
      (node (ref "U2") (pin "26") (pinfunction "VRTC_26") (pintype "passive"))
    )
    (net (code "89") (name "unconnected-(U3-PA0-Pad10)") (class "Default")
      (node (ref "U3") (pin "10") (pinfunction "PA0_10") (pintype "bidirectional"))
    )
    (net (code "90") (name "unconnected-(U3-PA1-Pad11)") (class "Default")
      (node (ref "U3") (pin "11") (pinfunction "PA1_11") (pintype "bidirectional"))
    )
    (net (code "91") (name "unconnected-(U3-PA2-Pad12)") (class "Default")
      (node (ref "U3") (pin "12") (pinfunction "PA2_12") (pintype "bidirectional"))
    )
    (net (code "92") (name "unconnected-(U3-PA8-Pad29)") (class "Default")
      (node (ref "U3") (pin "29") (pinfunction "PA8_29") (pintype "bidirectional"))
    )
    (net (code "93") (name "unconnected-(U3-PA11-Pad32)") (class "Default")
      (node (ref "U3") (pin "32") (pinfunction "PA11_32") (pintype "bidirectional"))
    )
    (net (code "94") (name "unconnected-(U3-PA12-Pad33)") (class "Default")
      (node (ref "U3") (pin "33") (pinfunction "PA12_33") (pintype "bidirectional"))
    )
    (net (code "95") (name "unconnected-(U3-PA15-Pad38)") (class "Default")
      (node (ref "U3") (pin "38") (pinfunction "PA15_38") (pintype "bidirectional"))
    )
    (net (code "96") (name "unconnected-(U3-PB3-Pad39)") (class "Default")
      (node (ref "U3") (pin "39") (pinfunction "PB3_39") (pintype "bidirectional"))
    )
    (net (code "97") (name "unconnected-(U3-PB4-Pad40)") (class "Default")
      (node (ref "U3") (pin "40") (pinfunction "PB4_40") (pintype "bidirectional"))
    )
    (net (code "98") (name "unconnected-(U3-PB5-Pad41)") (class "Default")
      (node (ref "U3") (pin "41") (pinfunction "PB5_41") (pintype "bidirectional"))
    )
    (net (code "99") (name "unconnected-(U3-PB6-Pad42)") (class "Default")
      (node (ref "U3") (pin "42") (pinfunction "PB6_42") (pintype "bidirectional"))
    )
    (net (code "100") (name "unconnected-(U3-PB7-Pad43)") (class "Default")
      (node (ref "U3") (pin "43") (pinfunction "PB7_43") (pintype "bidirectional"))
    )
    (net (code "101") (name "unconnected-(U3-PB8-Pad45)") (class "Default")
      (node (ref "U3") (pin "45") (pinfunction "PB8_45") (pintype "bidirectional"))
    )
    (net (code "102") (name "unconnected-(U3-PB9-Pad46)") (class "Default")
      (node (ref "U3") (pin "46") (pinfunction "PB9_46") (pintype "bidirectional"))
    )
    (net (code "103") (name "unconnected-(U3-PB12-Pad25)") (class "Default")
      (node (ref "U3") (pin "25") (pinfunction "PB12_25") (pintype "bidirectional"))
    )
    (net (code "104") (name "unconnected-(U3-PB13-Pad26)") (class "Default")
      (node (ref "U3") (pin "26") (pinfunction "PB13_26") (pintype "bidirectional"))
    )
    (net (code "105") (name "unconnected-(U3-PB14-Pad27)") (class "Default")
      (node (ref "U3") (pin "27") (pinfunction "PB14_27") (pintype "bidirectional"))
    )
    (net (code "106") (name "unconnected-(U3-PB15-Pad28)") (class "Default")
      (node (ref "U3") (pin "28") (pinfunction "PB15_28") (pintype "bidirectional"))
    )
    (net (code "107") (name "unconnected-(U3-PC13-Pad2)") (class "Default")
      (node (ref "U3") (pin "2") (pinfunction "PC13_2") (pintype "bidirectional"))
    )
  )
)
